# POWER.net
KiCad netlist of a schematic drawn in Altium Designer
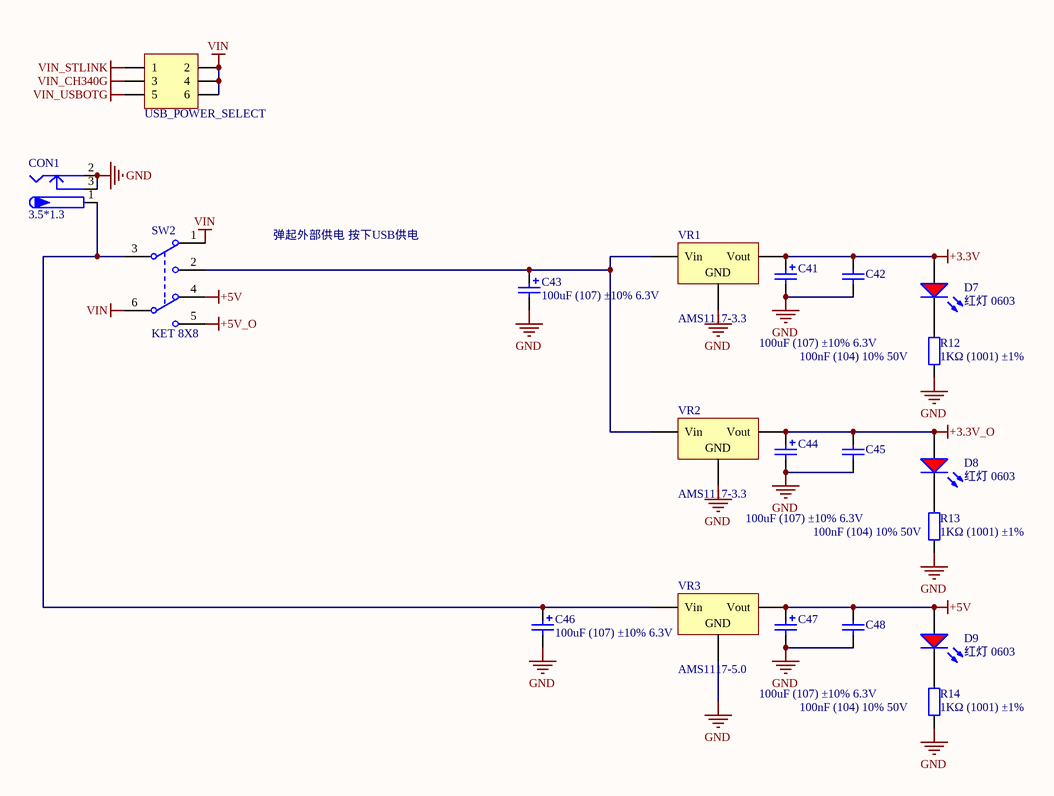
[diagram p0: POWER.SchDoc]

(export (version "E")
  (design (tool "Eeschema 10.0.6"))
  (components
    (comp (ref "C41")
      (value "100uF (107) ±10% 6.3V")
      (footprint "CASE-B_3528")
      (description "钽电容")
      (libsource (lib "Cap") (part "3528 100uF (107) 10% 6.3V"))
    )
    (comp (ref "C42")
      (value "100nF (104) 10% 50V")
      (footprint "0603_C")
      (description "贴片电容")
      (libsource (lib "Cap") (part "0603 100nF (104) 10% 50V"))
    )
    (comp (ref "C43")
      (value "100uF (107) ±10% 6.3V")
      (footprint "CASE-B_3528")
      (description "钽电容")
      (libsource (lib "Cap") (part "3528 100uF (107) 10% 6.3V"))
    )
    (comp (ref "C44")
      (value "100uF (107) ±10% 6.3V")
      (footprint "CASE-B_3528")
      (description "钽电容")
      (libsource (lib "Cap") (part "3528 100uF (107) 10% 6.3V"))
    )
    (comp (ref "C45")
      (value "100nF (104) 10% 50V")
      (footprint "0603_C")
      (description "贴片电容")
      (libsource (lib "Cap") (part "0603 100nF (104) 10% 50V"))
    )
    (comp (ref "C46")
      (value "100uF (107) ±10% 6.3V")
      (footprint "CASE-B_3528")
      (description "钽电容")
      (libsource (lib "Cap") (part "3528 100uF (107) 10% 6.3V"))
    )
    (comp (ref "C47")
      (value "100uF (107) ±10% 6.3V")
      (footprint "CASE-B_3528")
      (description "钽电容")
      (libsource (lib "Cap") (part "3528 100uF (107) 10% 6.3V"))
    )
    (comp (ref "C48")
      (value "100nF (104) 10% 50V")
      (footprint "0603_C")
      (description "贴片电容")
      (libsource (lib "Cap") (part "0603 100nF (104) 10% 50V"))
    )
    (comp (ref "CON1")
      (value "3.5*1.3")
      (footprint "DC-005")
      (description "低压电源接口")
      (fields (field (name "版权归属") "源创客"))
      (libsource (lib "4.1   - 接口类") (part "P-DC"))
    )
    (comp (ref "D7")
      (value "红灯 0603")
      (footprint "0603_LED_S1")
      (description "发光二极管")
      (libsource (lib "LED") (part "0603 红灯"))
    )
    (comp (ref "D8")
      (value "红灯 0603")
      (footprint "0603_LED_S1")
      (description "发光二极管")
      (libsource (lib "LED") (part "0603 红灯"))
    )
    (comp (ref "D9")
      (value "红灯 0603")
      (footprint "0603_LED_S1")
      (description "发光二极管")
      (libsource (lib "LED") (part "0603 红灯"))
    )
    (comp (ref "R12")
      (value "1KΩ (1001) ±1%")
      (footprint "0603_R")
      (description "贴片电阻")
      (libsource (lib "RES") (part "0603 1KΩ (1001) 1%"))
    )
    (comp (ref "R13")
      (value "1KΩ (1001) ±1%")
      (footprint "0603_R")
      (description "贴片电阻")
      (libsource (lib "RES") (part "0603 1KΩ (1001) 1%"))
    )
    (comp (ref "R14")
      (value "1KΩ (1001) ±1%")
      (footprint "0603_R")
      (description "贴片电阻")
      (libsource (lib "RES") (part "0603 1KΩ (1001) 1%"))
    )
    (comp (ref "SW2")
      (value "KET 8X8")
      (footprint "KFT DIP-8X8")
      (description "8*8自锁开关")
      (fields (field (name "版权归属") "源创客"))
      (libsource (lib "5.1   - 按键-开关") (part "KET 8X8"))
    )
    (comp (ref "USB_POWER_SELECT")
      (value "Header3X2")
      (footprint "HDR2.54-LI-2x3P")
      (description "3*2P接插件")
      (fields (field (name "版权归属") "源创客"))
      (libsource (lib "4.5   - 接插件-脚距2.54") (part "Header 3X2"))
    )
    (comp (ref "VR1")
      (value "AMS1117-3.3")
      (footprint "SOT-223")
      (description "低压差线性稳压(LDO)")
      (libsource (lib "LDO") (part "SOT-223 AMS1117-3.3"))
    )
    (comp (ref "VR2")
      (value "AMS1117-3.3")
      (footprint "SOT-223")
      (description "低压差线性稳压(LDO)")
      (libsource (lib "LDO") (part "SOT-223 AMS1117-3.3"))
    )
    (comp (ref "VR3")
      (value "AMS1117-5.0")
      (footprint "SOT-223")
      (description "低压差线性稳压(LDO)")
      (libsource (lib "LDO") (part "SOT-223 AMS1117-5.0"))
    )
  )
  (nets
    (net (code "1") (name "+3.3V") (class "Default")
      (node (ref "C41") (pin "1") (pinfunction "1_1") (pintype "passive"))
      (node (ref "C42") (pin "2") (pinfunction "2_2") (pintype "passive"))
      (node (ref "D7") (pin "A") (pinfunction "A_A") (pintype "passive"))
      (node (ref "VR1") (pin "2") (pinfunction "Vout_2") (pintype "passive"))
    )
    (net (code "2") (name "+3.3V_O") (class "Default")
      (node (ref "C44") (pin "1") (pinfunction "1_1") (pintype "passive"))
      (node (ref "C45") (pin "2") (pinfunction "2_2") (pintype "passive"))
      (node (ref "D8") (pin "A") (pinfunction "A_A") (pintype "passive"))
      (node (ref "VR2") (pin "2") (pinfunction "Vout_2") (pintype "passive"))
    )
    (net (code "3") (name "+5V") (class "Default")
      (node (ref "C47") (pin "1") (pinfunction "1_1") (pintype "passive"))
      (node (ref "C48") (pin "2") (pinfunction "2_2") (pintype "passive"))
      (node (ref "D9") (pin "A") (pinfunction "A_A") (pintype "passive"))
      (node (ref "SW2") (pin "4") (pinfunction "NO2_4") (pintype "passive"))
      (node (ref "VR3") (pin "2") (pinfunction "Vout_2") (pintype "passive"))
    )
    (net (code "4") (name "+5V_O") (class "Default")
      (node (ref "SW2") (pin "5") (pinfunction "COM2_5") (pintype "passive"))
    )
    (net (code "5") (name "GND") (class "Default")
      (node (ref "C41") (pin "2") (pinfunction "2_2") (pintype "passive"))
      (node (ref "C42") (pin "1") (pinfunction "1_1") (pintype "passive"))
      (node (ref "C43") (pin "2") (pinfunction "2_2") (pintype "passive"))
      (node (ref "C44") (pin "2") (pinfunction "2_2") (pintype "passive"))
      (node (ref "C45") (pin "1") (pinfunction "1_1") (pintype "passive"))
      (node (ref "C46") (pin "2") (pinfunction "2_2") (pintype "passive"))
      (node (ref "C47") (pin "2") (pinfunction "2_2") (pintype "passive"))
      (node (ref "C48") (pin "1") (pinfunction "1_1") (pintype "passive"))
      (node (ref "CON1") (pin "2") (pintype "power_in"))
      (node (ref "CON1") (pin "3") (pintype "power_in"))
      (node (ref "R12") (pin "1") (pinfunction "1_1") (pintype "passive"))
      (node (ref "R13") (pin "1") (pinfunction "1_1") (pintype "passive"))
      (node (ref "R14") (pin "1") (pinfunction "1_1") (pintype "passive"))
      (node (ref "VR1") (pin "1") (pinfunction "GND_1") (pintype "passive"))
      (node (ref "VR2") (pin "1") (pinfunction "GND_1") (pintype "passive"))
      (node (ref "VR3") (pin "1") (pinfunction "GND_1") (pintype "passive"))
    )
    (net (code "6") (name "Net-(D7-PadK)") (class "Default")
      (node (ref "D7") (pin "K") (pinfunction "K_K") (pintype "passive"))
      (node (ref "R12") (pin "2") (pinfunction "2_2") (pintype "passive"))
    )
    (net (code "7") (name "Net-(D8-PadK)") (class "Default")
      (node (ref "D8") (pin "K") (pinfunction "K_K") (pintype "passive"))
      (node (ref "R13") (pin "2") (pinfunction "2_2") (pintype "passive"))
    )
    (net (code "8") (name "Net-(D9-PadK)") (class "Default")
      (node (ref "D9") (pin "K") (pinfunction "K_K") (pintype "passive"))
      (node (ref "R14") (pin "2") (pinfunction "2_2") (pintype "passive"))
    )
    (net (code "9") (name "Net-(SW2-NO1)") (class "Default")
      (node (ref "C46") (pin "1") (pinfunction "1_1") (pintype "passive"))
      (node (ref "CON1") (pin "1") (pintype "power_in"))
      (node (ref "SW2") (pin "3") (pinfunction "NO1_3") (pintype "passive"))
      (node (ref "VR3") (pin "3") (pinfunction "Vin_3") (pintype "passive"))
    )
    (net (code "10") (name "Net-(VR1-Vin)") (class "Default")
      (node (ref "C43") (pin "1") (pinfunction "1_1") (pintype "passive"))
      (node (ref "SW2") (pin "2") (pinfunction "COM2_2") (pintype "passive"))
      (node (ref "VR1") (pin "3") (pinfunction "Vin_3") (pintype "passive"))
      (node (ref "VR2") (pin "3") (pinfunction "Vin_3") (pintype "passive"))
    )
    (net (code "11") (name "VIN") (class "Default")
      (node (ref "SW2") (pin "1") (pinfunction "NC1_1") (pintype "passive"))
      (node (ref "SW2") (pin "6") (pinfunction "NC2_6") (pintype "passive"))
      (node (ref "USB_POWER_SELECT") (pin "2") (pinfunction "2_2") (pintype "passive"))
      (node (ref "USB_POWER_SELECT") (pin "4") (pinfunction "4_4") (pintype "passive"))
      (node (ref "USB_POWER_SELECT") (pin "6") (pinfunction "6_6") (pintype "passive"))
    )
    (net (code "12") (name "VIN_CH340G") (class "Default")
      (node (ref "USB_POWER_SELECT") (pin "3") (pinfunction "3_3") (pintype "passive"))
    )
    (net (code "13") (name "VIN_STLINK") (class "Default")
      (node (ref "USB_POWER_SELECT") (pin "1") (pinfunction "1_1") (pintype "passive"))
    )
    (net (code "14") (name "VIN_USBOTG") (class "Default")
      (node (ref "USB_POWER_SELECT") (pin "5") (pinfunction "5_5") (pintype "passive"))
    )
  )
)
